# Steckkarte.net
KiCad netlist of a schematic drawn in EAGLE
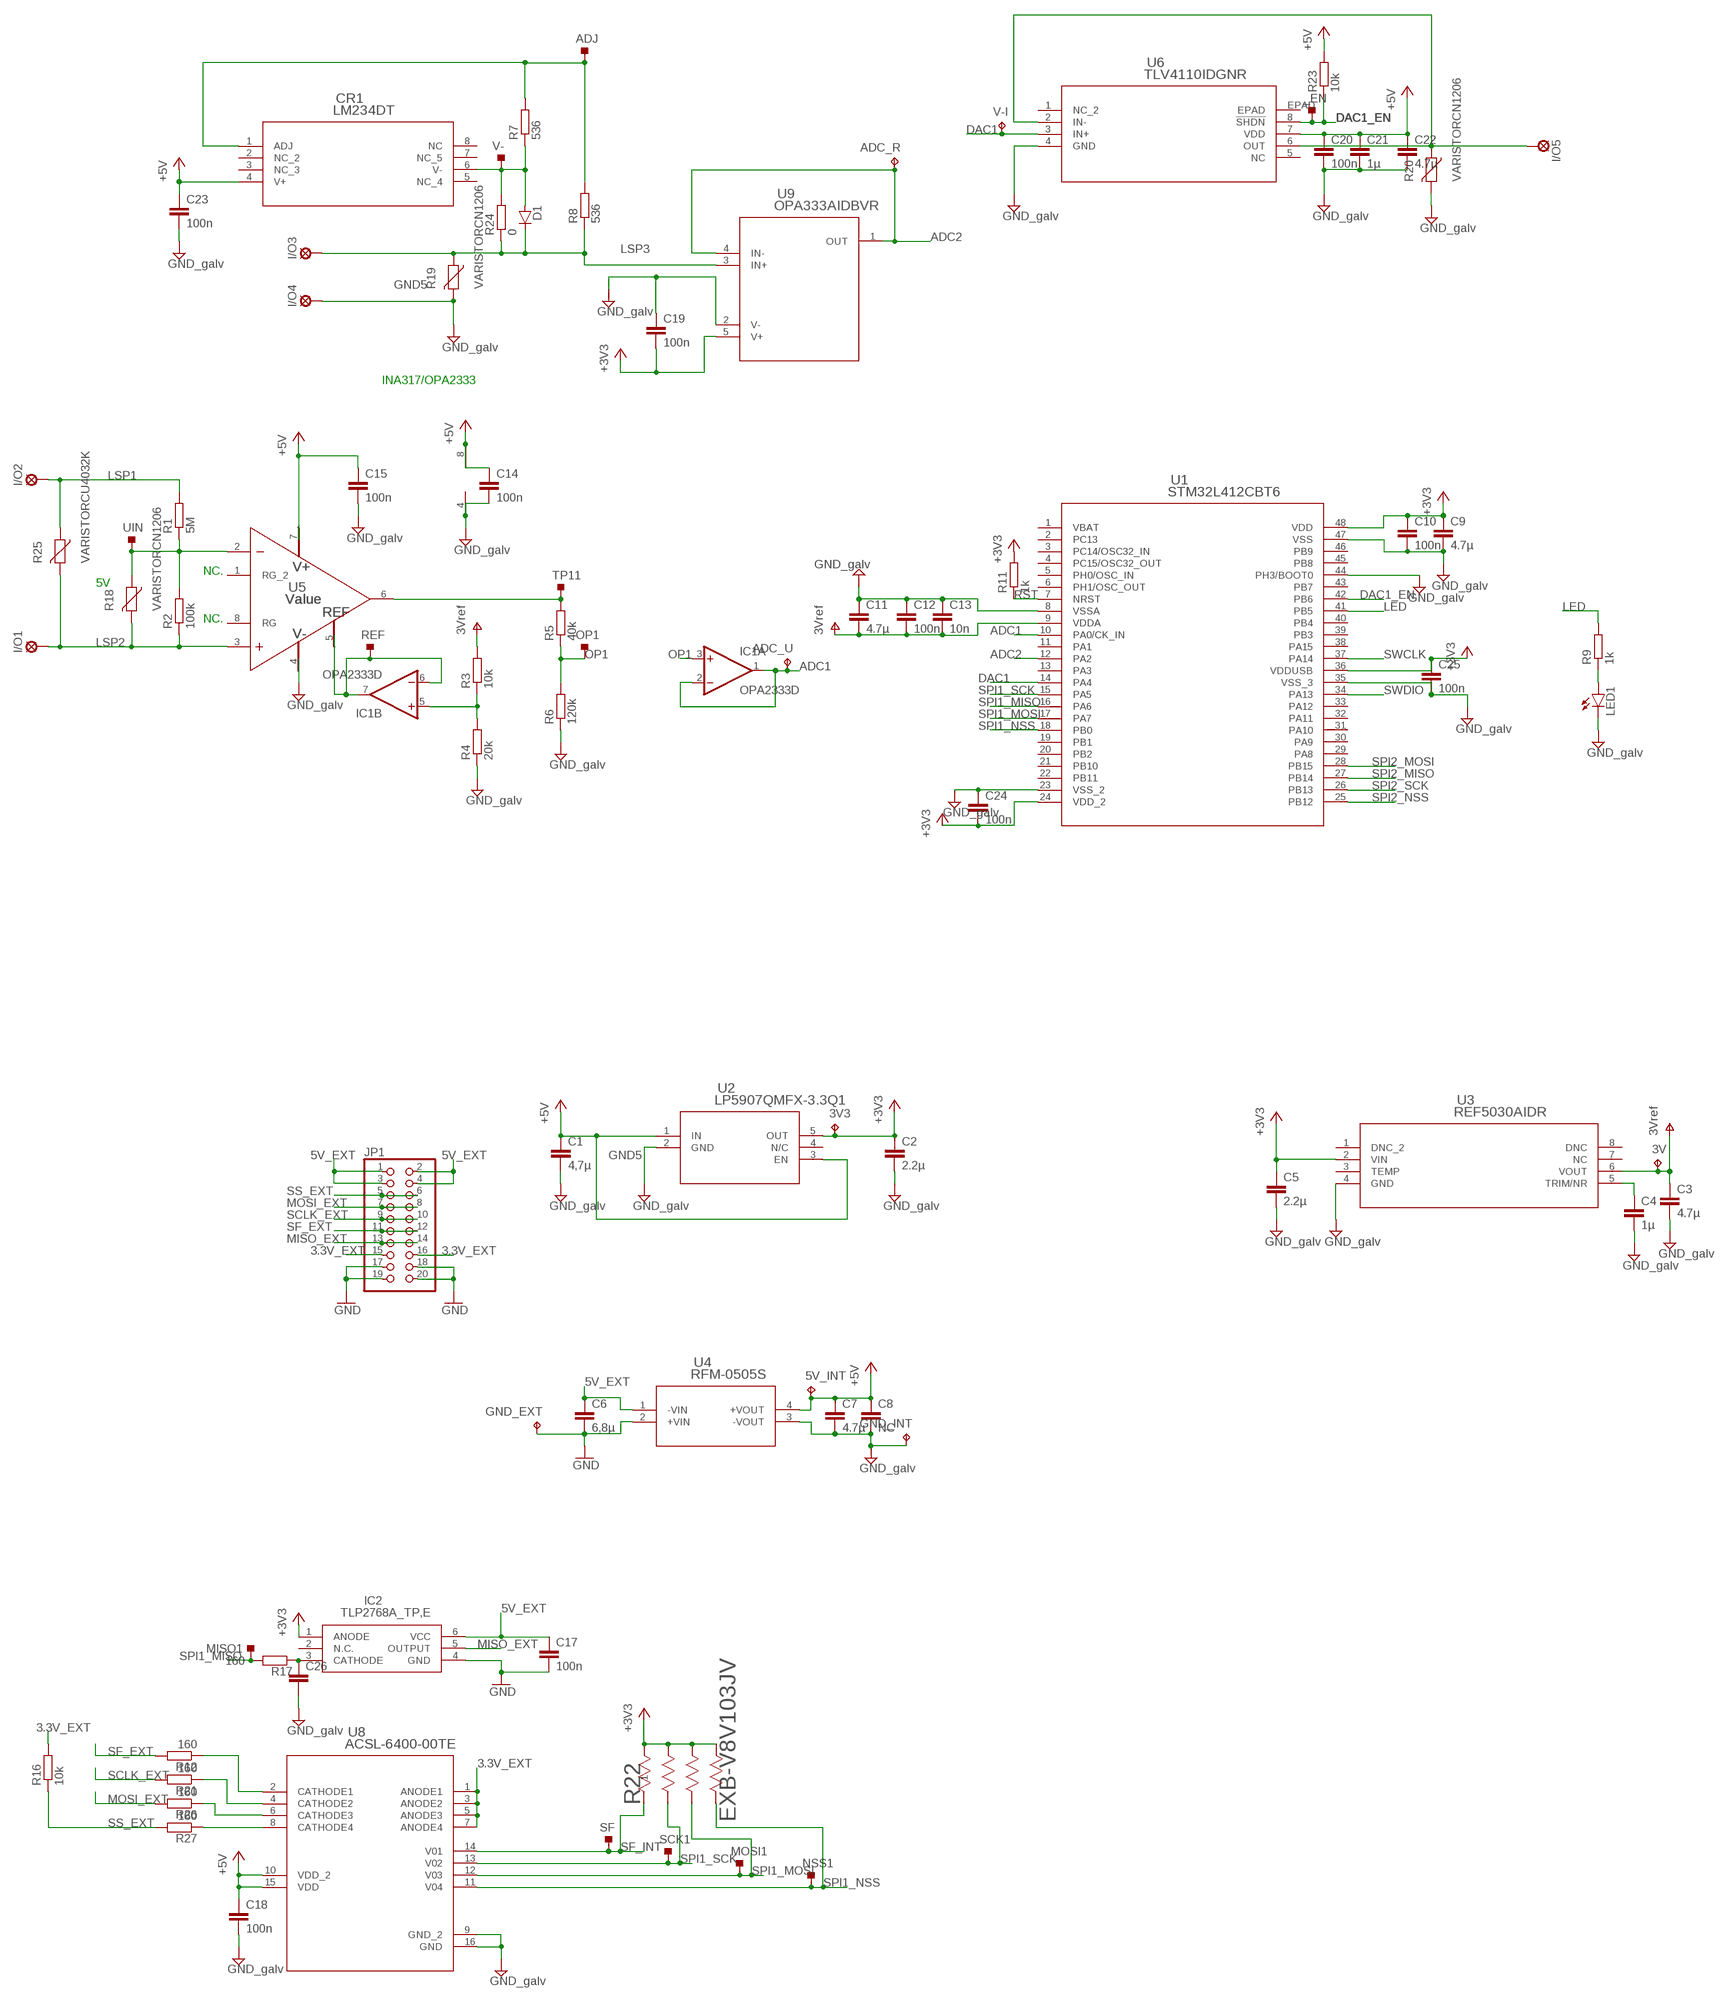
[diagram p0: schematic, sheet 1, part 1 of 2]
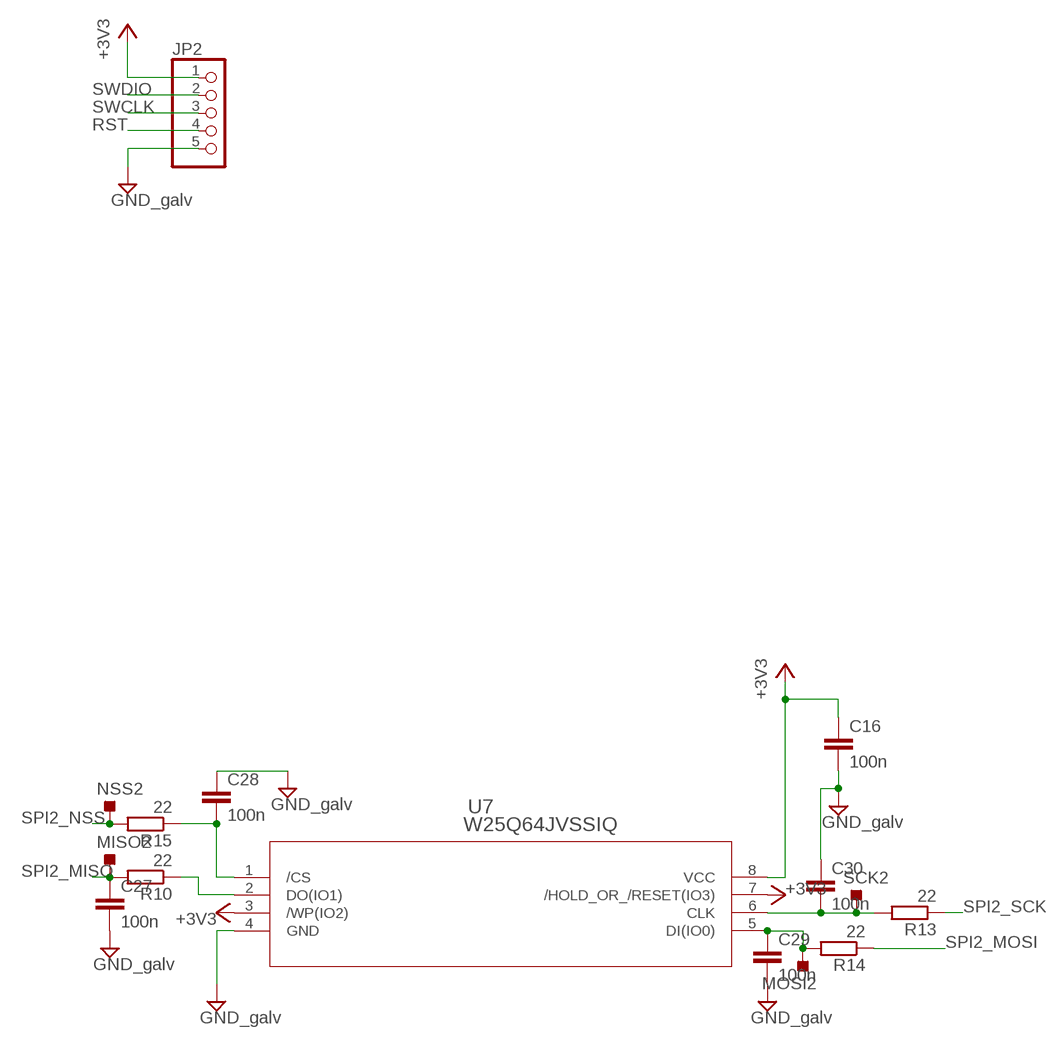
[diagram p1: schematic, sheet 1, part 2 of 2]

(export (version "E")
  (design (tool "Eeschema 10.0.6"))
  (components
    (comp (ref "3V")
      (value "TPPAD1-13")
      (footprint "eagle-import:P1-13")
      (libsource (lib "eagle-import") (part "TPPAD1-13"))
    )
    (comp (ref "3V3")
      (value "TPPAD1-13")
      (footprint "eagle-import:P1-13")
      (libsource (lib "eagle-import") (part "TPPAD1-13"))
    )
    (comp (ref "5V_INT")
      (value "TPPAD1-13")
      (footprint "eagle-import:P1-13")
      (libsource (lib "eagle-import") (part "TPPAD1-13"))
    )
    (comp (ref "ADC_R")
      (value "TPPAD1-13")
      (footprint "eagle-import:P1-13")
      (libsource (lib "eagle-import") (part "TPPAD1-13"))
    )
    (comp (ref "ADC_U")
      (value "TPPAD1-13")
      (footprint "eagle-import:P1-13")
      (libsource (lib "eagle-import") (part "TPPAD1-13"))
    )
    (comp (ref "ADJ")
      (value "TESTPOINT_TPS-SMD-10SN")
      (footprint "eagle-import:TESTPOINT_SMD-10SN")
      (libsource (lib "eagle-import") (part "TESTPOINT_TPS-SMD-10SN"))
    )
    (comp (ref "C1")
      (value "4,7µ")
      (footprint "eagle-import:C0603K")
      (libsource (lib "eagle-import") (part "C-EUC0603K"))
    )
    (comp (ref "C2")
      (value "2.2µ")
      (footprint "eagle-import:C0603K")
      (libsource (lib "eagle-import") (part "C-EUC0603K"))
    )
    (comp (ref "C3")
      (value "4.7µ")
      (footprint "eagle-import:C0603K")
      (libsource (lib "eagle-import") (part "C-EUC0603K"))
    )
    (comp (ref "C4")
      (value "1µ")
      (footprint "eagle-import:C0603K")
      (libsource (lib "eagle-import") (part "C-EUC0603K"))
    )
    (comp (ref "C5")
      (value "2.2µ")
      (footprint "eagle-import:C0603K")
      (libsource (lib "eagle-import") (part "C-EUC0603K"))
    )
    (comp (ref "C6")
      (value "6,8µ")
      (footprint "eagle-import:C0603K")
      (libsource (lib "eagle-import") (part "resistor_348_C-EUC0603K"))
    )
    (comp (ref "C7")
      (value "4.7µ")
      (footprint "eagle-import:C0603K")
      (libsource (lib "eagle-import") (part "resistor_348_C-EUC0603K"))
    )
    (comp (ref "C8")
      (value "NC")
      (footprint "eagle-import:C0603K")
      (libsource (lib "eagle-import") (part "resistor_348_C-EUC0603K"))
    )
    (comp (ref "C9")
      (value "4.7µ")
      (footprint "eagle-import:C0603K")
      (libsource (lib "eagle-import") (part "C-EUC0603K"))
    )
    (comp (ref "C10")
      (value "100n")
      (footprint "eagle-import:C0603K")
      (libsource (lib "eagle-import") (part "C-EUC0603K"))
    )
    (comp (ref "C11")
      (value "4.7µ")
      (footprint "eagle-import:C0603K")
      (libsource (lib "eagle-import") (part "C-EUC0603K"))
    )
    (comp (ref "C12")
      (value "100n")
      (footprint "eagle-import:C0603K")
      (libsource (lib "eagle-import") (part "C-EUC0603K"))
    )
    (comp (ref "C13")
      (value "10n")
      (footprint "eagle-import:C0603K")
      (libsource (lib "eagle-import") (part "C-EUC0603K"))
    )
    (comp (ref "C14")
      (value "100n")
      (footprint "eagle-import:C0603K")
      (libsource (lib "eagle-import") (part "C-EUC0603K"))
    )
    (comp (ref "C15")
      (value "100n")
      (footprint "eagle-import:C0603K")
      (libsource (lib "eagle-import") (part "C-EUC0603K"))
    )
    (comp (ref "C16")
      (value "100n")
      (footprint "eagle-import:C0603K")
      (libsource (lib "eagle-import") (part "C-EUC0603K"))
    )
    (comp (ref "C17")
      (value "100n")
      (footprint "eagle-import:C0603K")
      (libsource (lib "eagle-import") (part "C-EUC0603K"))
    )
    (comp (ref "C18")
      (value "100n")
      (footprint "eagle-import:C0603K")
      (libsource (lib "eagle-import") (part "C-EUC0603K"))
    )
    (comp (ref "C19")
      (value "100n")
      (footprint "eagle-import:C0603K")
      (libsource (lib "eagle-import") (part "C-EUC0603K"))
    )
    (comp (ref "C20")
      (value "100n")
      (footprint "eagle-import:C0603K")
      (libsource (lib "eagle-import") (part "C-EUC0603K"))
    )
    (comp (ref "C21")
      (value "1µ")
      (footprint "eagle-import:C0603K")
      (libsource (lib "eagle-import") (part "C-EUC0603K"))
    )
    (comp (ref "C22")
      (value "4.7µ")
      (footprint "eagle-import:C0603K")
      (libsource (lib "eagle-import") (part "C-EUC0603K"))
    )
    (comp (ref "C23")
      (value "100n")
      (footprint "eagle-import:C0603K")
      (libsource (lib "eagle-import") (part "C-EUC0603K"))
    )
    (comp (ref "C24")
      (value "100n")
      (footprint "eagle-import:C0603K")
      (libsource (lib "eagle-import") (part "C-EUC0603K"))
    )
    (comp (ref "C25")
      (value "100n")
      (footprint "eagle-import:C0603K")
      (libsource (lib "eagle-import") (part "C-EUC0603K"))
    )
    (comp (ref "C26")
      (value "C-EUC0603K")
      (footprint "eagle-import:C0603K")
      (libsource (lib "eagle-import") (part "C-EUC0603K"))
    )
    (comp (ref "C27")
      (value "100n")
      (footprint "eagle-import:C0603K")
      (libsource (lib "eagle-import") (part "C-EUC0603K"))
    )
    (comp (ref "C28")
      (value "100n")
      (footprint "eagle-import:C0603K")
      (libsource (lib "eagle-import") (part "C-EUC0603K"))
    )
    (comp (ref "C29")
      (value "100n")
      (footprint "eagle-import:C0603K")
      (libsource (lib "eagle-import") (part "C-EUC0603K"))
    )
    (comp (ref "C30")
      (value "100n")
      (footprint "eagle-import:C0603K")
      (libsource (lib "eagle-import") (part "C-EUC0603K"))
    )
    (comp (ref "CR1")
      (value "LM234DT")
      (footprint "eagle-import:SO-8")
      (libsource (lib "eagle-import") (part "LM234DT"))
    )
    (comp (ref "D1")
      (value "D-SOD123")
      (footprint "eagle-import:SOD123")
      (libsource (lib "eagle-import") (part "D-SOD123"))
    )
    (comp (ref "GND_EXT")
      (value "TPPAD1-13")
      (footprint "eagle-import:P1-13")
      (libsource (lib "eagle-import") (part "TPPAD1-13"))
    )
    (comp (ref "GND_INT")
      (value "TPPAD1-13")
      (footprint "eagle-import:P1-13")
      (libsource (lib "eagle-import") (part "TPPAD1-13"))
    )
    (comp (ref "I/O1")
      (value "SE14")
      (footprint "eagle-import:SE14")
      (libsource (lib "eagle-import") (part "SE14"))
    )
    (comp (ref "I/O2")
      (value "SE14")
      (footprint "eagle-import:SE14")
      (libsource (lib "eagle-import") (part "SE14"))
    )
    (comp (ref "I/O3")
      (value "SE14")
      (footprint "eagle-import:SE14")
      (libsource (lib "eagle-import") (part "SE14"))
    )
    (comp (ref "I/O4")
      (value "SE14")
      (footprint "eagle-import:SE14")
      (libsource (lib "eagle-import") (part "SE14"))
    )
    (comp (ref "I/O5")
      (value "SE14")
      (footprint "eagle-import:SE14")
      (libsource (lib "eagle-import") (part "SE14"))
    )
    (comp (ref "IC1")
      (value "OPA2333D")
      (footprint "eagle-import:SO08")
      (libsource (lib "eagle-import") (part "OPA2333D"))
    )
    (comp (ref "IC2")
      (value "TLP2768A_TP,E")
      (footprint "eagle-import:SOIC127P1000X220-6N")
      (fields
        (field (name "MANUFACTURER_PART_NUMBER") "TLP2768A(TP,E")
        (field (name "MOUSER_PART_NUMBER") "757-TLP2768ATPE")
      )
      (libsource (lib "eagle-import") (part "TLP2768A_TP,E"))
    )
    (comp (ref "JP1")
      (value "PINHD-2X10/90")
      (footprint "eagle-import:2X10_90")
      (libsource (lib "eagle-import") (part "PINHD-2X10/90"))
    )
    (comp (ref "JP2")
      (value "PINHD-1X5")
      (footprint "eagle-import:1X05")
      (libsource (lib "eagle-import") (part "PINHD-1X5"))
    )
    (comp (ref "LED1")
      (value "LED5MM")
      (footprint "eagle-import:LED5MM")
      (libsource (lib "eagle-import") (part "LED5MM"))
    )
    (comp (ref "MISO1")
      (value "TESTPOINT_TPS-SMD-10SN")
      (footprint "eagle-import:TESTPOINT_SMD-10SN")
      (libsource (lib "eagle-import") (part "TESTPOINT_TPS-SMD-10SN"))
    )
    (comp (ref "MISO2")
      (value "TESTPOINT_TPS-SMD-10SN")
      (footprint "eagle-import:TESTPOINT_SMD-10SN")
      (libsource (lib "eagle-import") (part "TESTPOINT_TPS-SMD-10SN"))
    )
    (comp (ref "MOSI1")
      (value "TESTPOINT_TPS-SMD-10SN")
      (footprint "eagle-import:TESTPOINT_SMD-10SN")
      (libsource (lib "eagle-import") (part "TESTPOINT_TPS-SMD-10SN"))
    )
    (comp (ref "MOSI2")
      (value "TESTPOINT_TPS-SMD-10SN")
      (footprint "eagle-import:TESTPOINT_SMD-10SN")
      (libsource (lib "eagle-import") (part "TESTPOINT_TPS-SMD-10SN"))
    )
    (comp (ref "NSS1")
      (value "TESTPOINT_TPS-SMD-10SN")
      (footprint "eagle-import:TESTPOINT_SMD-10SN")
      (libsource (lib "eagle-import") (part "TESTPOINT_TPS-SMD-10SN"))
    )
    (comp (ref "NSS2")
      (value "TESTPOINT_TPS-SMD-10SN")
      (footprint "eagle-import:TESTPOINT_SMD-10SN")
      (libsource (lib "eagle-import") (part "TESTPOINT_TPS-SMD-10SN"))
    )
    (comp (ref "OP1")
      (value "TESTPOINT_TPS-SMD-10SN")
      (footprint "eagle-import:TESTPOINT_SMD-10SN")
      (libsource (lib "eagle-import") (part "TESTPOINT_TPS-SMD-10SN"))
    )
    (comp (ref "R1")
      (value "5M")
      (footprint "eagle-import:R1206")
      (libsource (lib "eagle-import") (part "R-EU_R1206"))
    )
    (comp (ref "R2")
      (value "100k")
      (footprint "eagle-import:R1206")
      (libsource (lib "eagle-import") (part "R-EU_R1206"))
    )
    (comp (ref "R3")
      (value "10k")
      (footprint "eagle-import:R0603")
      (libsource (lib "eagle-import") (part "R-EU_R0603"))
    )
    (comp (ref "R4")
      (value "20k")
      (footprint "eagle-import:R0603")
      (libsource (lib "eagle-import") (part "R-EU_R0603"))
    )
    (comp (ref "R5")
      (value "40k")
      (footprint "eagle-import:R0603")
      (libsource (lib "eagle-import") (part "R-EU_R0603"))
    )
    (comp (ref "R6")
      (value "120k")
      (footprint "eagle-import:R0603")
      (libsource (lib "eagle-import") (part "R-EU_R0603"))
    )
    (comp (ref "R7")
      (value "536")
      (footprint "eagle-import:R0603")
      (libsource (lib "eagle-import") (part "R-EU_R0603"))
    )
    (comp (ref "R8")
      (value "536")
      (footprint "eagle-import:R0603")
      (libsource (lib "eagle-import") (part "R-EU_R0603"))
    )
    (comp (ref "R9")
      (value "1k")
      (footprint "eagle-import:R0603")
      (libsource (lib "eagle-import") (part "R-EU_R0603"))
    )
    (comp (ref "R10")
      (value "22")
      (footprint "eagle-import:R0603")
      (libsource (lib "eagle-import") (part "R-EU_R0603"))
    )
    (comp (ref "R11")
      (value "1k")
      (footprint "eagle-import:R0603")
      (libsource (lib "eagle-import") (part "R-EU_R0603"))
    )
    (comp (ref "R12")
      (value "160")
      (footprint "eagle-import:R0603")
      (libsource (lib "eagle-import") (part "R-EU_R0603"))
    )
    (comp (ref "R13")
      (value "22")
      (footprint "eagle-import:R0603")
      (libsource (lib "eagle-import") (part "R-EU_R0603"))
    )
    (comp (ref "R14")
      (value "22")
      (footprint "eagle-import:R0603")
      (libsource (lib "eagle-import") (part "R-EU_R0603"))
    )
    (comp (ref "R15")
      (value "22")
      (footprint "eagle-import:R0603")
      (libsource (lib "eagle-import") (part "R-EU_R0603"))
    )
    (comp (ref "R16")
      (value "10k")
      (footprint "eagle-import:R0603")
      (libsource (lib "eagle-import") (part "R-EU_R0603"))
    )
    (comp (ref "R17")
      (value "160")
      (footprint "eagle-import:R0603")
      (libsource (lib "eagle-import") (part "R-EU_R0603"))
    )
    (comp (ref "R18")
      (value "VARISTORCN1206")
      (footprint "eagle-import:CT_CN1206")
      (libsource (lib "eagle-import") (part "VARISTORCN1206"))
    )
    (comp (ref "R19")
      (value "VARISTORCN1206")
      (footprint "eagle-import:CT_CN1206")
      (libsource (lib "eagle-import") (part "VARISTORCN1206"))
    )
    (comp (ref "R20")
      (value "VARISTORCN1206")
      (footprint "eagle-import:CT_CN1206")
      (libsource (lib "eagle-import") (part "VARISTORCN1206"))
    )
    (comp (ref "R21")
      (value "160")
      (footprint "eagle-import:R0603")
      (libsource (lib "eagle-import") (part "R-EU_R0603"))
    )
    (comp (ref "R22")
      (value "EXB-V8V103JV")
      (footprint "eagle-import:EXBV8V")
      (libsource (lib "eagle-import") (part "EXB-V8V103JV"))
    )
    (comp (ref "R23")
      (value "10k")
      (footprint "eagle-import:R0603")
      (libsource (lib "eagle-import") (part "R-EU_R0603"))
    )
    (comp (ref "R24")
      (value "0")
      (footprint "eagle-import:R0603")
      (libsource (lib "eagle-import") (part "R-EU_R0603"))
    )
    (comp (ref "R25")
      (value "VARISTORCU4032K")
      (footprint "eagle-import:CU4032K")
      (libsource (lib "eagle-import") (part "VARISTORCU4032K"))
    )
    (comp (ref "R26")
      (value "160")
      (footprint "eagle-import:R0603")
      (libsource (lib "eagle-import") (part "R-EU_R0603"))
    )
    (comp (ref "R27")
      (value "160")
      (footprint "eagle-import:R0603")
      (libsource (lib "eagle-import") (part "R-EU_R0603"))
    )
    (comp (ref "REF")
      (value "TESTPOINT_TPS-SMD-10SN")
      (footprint "eagle-import:TESTPOINT_SMD-10SN")
      (libsource (lib "eagle-import") (part "TESTPOINT_TPS-SMD-10SN"))
    )
    (comp (ref "SCK1")
      (value "TESTPOINT_TPS-SMD-10SN")
      (footprint "eagle-import:TESTPOINT_SMD-10SN")
      (libsource (lib "eagle-import") (part "TESTPOINT_TPS-SMD-10SN"))
    )
    (comp (ref "SCK2")
      (value "TESTPOINT_TPS-SMD-10SN")
      (footprint "eagle-import:TESTPOINT_SMD-10SN")
      (libsource (lib "eagle-import") (part "TESTPOINT_TPS-SMD-10SN"))
    )
    (comp (ref "SF")
      (value "TESTPOINT_TPS-SMD-10SN")
      (footprint "eagle-import:TESTPOINT_SMD-10SN")
      (libsource (lib "eagle-import") (part "TESTPOINT_TPS-SMD-10SN"))
    )
    (comp (ref "TP11")
      (value "TESTPOINT_TPS-SMD-10SN")
      (footprint "eagle-import:TESTPOINT_SMD-10SN")
      (libsource (lib "eagle-import") (part "TESTPOINT_TPS-SMD-10SN"))
    )
    (comp (ref "U1")
      (value "STM32L412CBT6")
      (footprint "eagle-import:LQFP-48")
      (fields (field (name "COPYRIGHT") "Copyright (C) 2018 Accelerated Designs. All rights reserved"))
      (libsource (lib "eagle-import") (part "STM32L412CBT6"))
    )
    (comp (ref "U2")
      (value "LP5907QMFX-3.3Q1")
      (footprint "eagle-import:DBV5")
      (libsource (lib "eagle-import") (part "LP5907QMFX-3.3Q1"))
    )
    (comp (ref "U3")
      (value "REF5030AIDR")
      (footprint "eagle-import:D8")
      (libsource (lib "eagle-import") (part "REF5030AIDR"))
    )
    (comp (ref "U4")
      (value "RFM-0505S")
      (footprint "eagle-import:RFM-0505S")
      (fields (field (name "COPYRIGHT") "Copyright (C) 2018 Accelerated Designs. All rights reserved"))
      (libsource (lib "eagle-import") (part "RFM-0505S"))
    )
    (comp (ref "U5")
      (value "Value")
      (footprint "eagle-import:DGK0008A_N")
      (fields (field (name "MANUFACTURER") "Texas Instruments") (field (name "PARTNUMBER") "INA317IDGKR"))
      (libsource (lib "eagle-import") (part "INA317IDGKR"))
    )
    (comp (ref "U6")
      (value "TLV4110IDGNR")
      (footprint "eagle-import:DGN8_1P89X1P57")
      (fields
        (field (name "GENERIC_PART_NUMBER") "TLV4110")
        (field (name "MANUFACTURER") "Texas Instruments")
      )
      (libsource (lib "eagle-import") (part "TLV4110IDGNR"))
    )
    (comp (ref "U7")
      (value "W25Q64JVSSIQ")
      (footprint "eagle-import:SOIC-8_5P28X5P28")
      (fields (field (name "COPYRIGHT") "Copyright (C) 2018 Accelerated Designs. All rights reserved"))
      (libsource (lib "eagle-import") (part "W25Q64JVSSIQ"))
    )
    (comp (ref "U8")
      (value "ACSL-6400-00TE")
      (footprint "eagle-import:SOIC_6400-00TE")
      (fields (field (name "COPYRIGHT") "Copyright (C) 2018 Accelerated Designs. All rights reserved"))
      (libsource (lib "eagle-import") (part "ACSL-6400-00TE"))
    )
    (comp (ref "U9")
      (value "OPA333AIDBVR")
      (footprint "eagle-import:DBV5")
      (fields (field (name "GENERIC_PART_NUMBER") "OPA333") (field (name "MANUFACTURER") "Texas Instruments"))
      (libsource (lib "eagle-import") (part "OPA333AIDBVR"))
    )
    (comp (ref "UIN")
      (value "TESTPOINT_TPS-SMD-10SN")
      (footprint "eagle-import:TESTPOINT_SMD-10SN")
      (libsource (lib "eagle-import") (part "TESTPOINT_TPS-SMD-10SN"))
    )
    (comp (ref "V-")
      (value "TESTPOINT_TPS-SMD-10SN")
      (footprint "eagle-import:TESTPOINT_SMD-10SN")
      (libsource (lib "eagle-import") (part "TESTPOINT_TPS-SMD-10SN"))
    )
    (comp (ref "V-I")
      (value "TPPAD1-13")
      (footprint "eagle-import:P1-13")
      (libsource (lib "eagle-import") (part "TPPAD1-13"))
    )
    (comp (ref "_EN")
      (value "TESTPOINT_TPS-SMD-10SN")
      (footprint "eagle-import:TESTPOINT_SMD-10SN")
      (libsource (lib "eagle-import") (part "TESTPOINT_TPS-SMD-10SN"))
    )
  )
  (nets
    (net (code "1") (name "+3V3") (class "Default")
      (node (ref "3V3") (pin "TP") (pinfunction "TP_TP") (pintype "input"))
      (node (ref "C10") (pin "1") (pinfunction "1_1") (pintype "passive"))
      (node (ref "C16") (pin "1") (pinfunction "1_1") (pintype "passive"))
      (node (ref "C19") (pin "2") (pinfunction "2_2") (pintype "passive"))
      (node (ref "C2") (pin "1") (pinfunction "1_1") (pintype "passive"))
      (node (ref "C24") (pin "2") (pinfunction "2_2") (pintype "passive"))
      (node (ref "C25") (pin "1") (pinfunction "1_1") (pintype "passive"))
      (node (ref "C5") (pin "1") (pinfunction "1_1") (pintype "passive"))
      (node (ref "C9") (pin "1") (pinfunction "1_1") (pintype "passive"))
      (node (ref "IC2") (pin "1") (pinfunction "ANODE_1") (pintype "bidirectional"))
      (node (ref "JP2") (pin "1") (pinfunction "1_1") (pintype "passive"))
      (node (ref "R11") (pin "2") (pinfunction "2_2") (pintype "passive"))
      (node (ref "R22") (pin "5") (pinfunction "5_5") (pintype "passive"))
      (node (ref "R22") (pin "6") (pinfunction "6_6") (pintype "passive"))
      (node (ref "R22") (pin "7") (pinfunction "7_7") (pintype "passive"))
      (node (ref "R22") (pin "8") (pinfunction "8_8") (pintype "passive"))
      (node (ref "U1") (pin "24") (pinfunction "VDD_2_24") (pintype "power_in"))
      (node (ref "U1") (pin "36") (pinfunction "VDDUSB_36") (pintype "power_in"))
      (node (ref "U1") (pin "48") (pinfunction "VDD_48") (pintype "power_in"))
      (node (ref "U2") (pin "5") (pinfunction "OUT_5") (pintype "output"))
      (node (ref "U3") (pin "2") (pinfunction "VIN_2") (pintype "input"))
      (node (ref "U7") (pin "3") (pinfunction "/WP(IO2)_3") (pintype "passive"))
      (node (ref "U7") (pin "7") (pinfunction "/HOLD_OR_/RESET(IO3)_7") (pintype "passive"))
      (node (ref "U7") (pin "8") (pinfunction "VCC_8") (pintype "power_in"))
      (node (ref "U9") (pin "5") (pinfunction "V+_5") (pintype "power_in"))
    )
    (net (code "2") (name "+5V") (class "Default")
      (node (ref "5V_INT") (pin "TP") (pinfunction "TP_TP") (pintype "input"))
      (node (ref "C1") (pin "1") (pinfunction "1_1") (pintype "passive"))
      (node (ref "C14") (pin "1") (pinfunction "1_1") (pintype "passive"))
      (node (ref "C15") (pin "1") (pinfunction "1_1") (pintype "passive"))
      (node (ref "C18") (pin "1") (pinfunction "1_1") (pintype "passive"))
      (node (ref "C20") (pin "1") (pinfunction "1_1") (pintype "passive"))
      (node (ref "C21") (pin "1") (pinfunction "1_1") (pintype "passive"))
      (node (ref "C22") (pin "1") (pinfunction "1_1") (pintype "passive"))
      (node (ref "C23") (pin "1") (pinfunction "1_1") (pintype "passive"))
      (node (ref "C7") (pin "1") (pinfunction "1_1") (pintype "passive"))
      (node (ref "C8") (pin "1") (pinfunction "1_1") (pintype "passive"))
      (node (ref "CR1") (pin "4") (pinfunction "V+_4") (pintype "power_in"))
      (node (ref "IC1") (pin "8") (pinfunction "V+_8") (pintype "power_in"))
      (node (ref "R23") (pin "2") (pinfunction "2_2") (pintype "passive"))
      (node (ref "U2") (pin "1") (pinfunction "IN_1") (pintype "input"))
      (node (ref "U2") (pin "3") (pinfunction "EN_3") (pintype "input"))
      (node (ref "U4") (pin "4") (pinfunction "+VOUT_4") (pintype "output"))
      (node (ref "U5") (pin "7") (pinfunction "V+_7") (pintype "power_in"))
      (node (ref "U6") (pin "7") (pinfunction "VDD_7") (pintype "power_in"))
      (node (ref "U8") (pin "10") (pinfunction "VDD_2_10") (pintype "power_in"))
      (node (ref "U8") (pin "15") (pinfunction "VDD_15") (pintype "power_in"))
    )
    (net (code "3") (name "/3.3V_EXT") (class "Default")
      (node (ref "JP1") (pin "15") (pinfunction "15_15") (pintype "passive"))
      (node (ref "JP1") (pin "16") (pinfunction "16_16") (pintype "passive"))
      (node (ref "R16") (pin "2") (pinfunction "2_2") (pintype "passive"))
      (node (ref "U8") (pin "1") (pinfunction "ANODE1_1") (pintype "bidirectional"))
      (node (ref "U8") (pin "3") (pinfunction "ANODE2_3") (pintype "bidirectional"))
      (node (ref "U8") (pin "5") (pinfunction "ANODE3_5") (pintype "bidirectional"))
      (node (ref "U8") (pin "7") (pinfunction "ANODE4_7") (pintype "bidirectional"))
    )
    (net (code "4") (name "/5V_EXT") (class "Default")
      (node (ref "C17") (pin "1") (pinfunction "1_1") (pintype "passive"))
      (node (ref "C6") (pin "1") (pinfunction "1_1") (pintype "passive"))
      (node (ref "IC2") (pin "6") (pinfunction "VCC_6") (pintype "bidirectional"))
      (node (ref "JP1") (pin "1") (pinfunction "1_1") (pintype "passive"))
      (node (ref "JP1") (pin "2") (pinfunction "2_2") (pintype "passive"))
      (node (ref "JP1") (pin "3") (pinfunction "3_3") (pintype "passive"))
      (node (ref "JP1") (pin "4") (pinfunction "4_4") (pintype "passive"))
      (node (ref "U4") (pin "1") (pinfunction "-VIN_1") (pintype "input"))
    )
    (net (code "5") (name "/ADC1") (class "Default")
      (node (ref "ADC_U") (pin "TP") (pinfunction "TP_TP") (pintype "input"))
      (node (ref "IC1") (pin "1") (pinfunction "OUT_1") (pintype "output"))
      (node (ref "IC1") (pin "2") (pinfunction "-IN_2") (pintype "input"))
      (node (ref "U1") (pin "10") (pinfunction "PA0/CK_IN_10") (pintype "bidirectional"))
    )
    (net (code "6") (name "/ADC2") (class "Default")
      (node (ref "ADC_R") (pin "TP") (pinfunction "TP_TP") (pintype "input"))
      (node (ref "U1") (pin "12") (pinfunction "PA2_12") (pintype "bidirectional"))
      (node (ref "U9") (pin "1") (pinfunction "OUT_1") (pintype "output"))
      (node (ref "U9") (pin "4") (pinfunction "IN-_4") (pintype "input"))
    )
    (net (code "7") (name "/DAC1") (class "Default")
      (node (ref "U1") (pin "14") (pinfunction "PA4_14") (pintype "bidirectional"))
      (node (ref "U6") (pin "3") (pinfunction "IN+_3") (pintype "input"))
      (node (ref "V-I") (pin "TP") (pinfunction "TP_TP") (pintype "input"))
    )
    (net (code "8") (name "/DAC1_EN") (class "Default")
      (node (ref "R23") (pin "1") (pinfunction "1_1") (pintype "passive"))
      (node (ref "U1") (pin "42") (pinfunction "PB6_42") (pintype "bidirectional"))
      (node (ref "U6") (pin "8") (pinfunction "~{SHDN}_8") (pintype "passive"))
      (node (ref "_EN") (pin "TP") (pinfunction "TP_TP") (pintype "passive"))
    )
    (net (code "9") (name "/LED") (class "Default")
      (node (ref "R9") (pin "2") (pinfunction "2_2") (pintype "passive"))
      (node (ref "U1") (pin "41") (pinfunction "PB5_41") (pintype "bidirectional"))
    )
    (net (code "10") (name "/LSP1") (class "Default")
      (node (ref "I/O2") (pin "MP") (pinfunction "MP_MP") (pintype "passive"))
      (node (ref "R1") (pin "2") (pinfunction "2_2") (pintype "passive"))
      (node (ref "R25") (pin "1") (pinfunction "1_1") (pintype "passive"))
    )
    (net (code "11") (name "/LSP2") (class "Default")
      (node (ref "I/O1") (pin "MP") (pinfunction "MP_MP") (pintype "passive"))
      (node (ref "R18") (pin "2") (pinfunction "2_2") (pintype "passive"))
      (node (ref "R2") (pin "1") (pinfunction "1_1") (pintype "passive"))
      (node (ref "R25") (pin "2") (pinfunction "2_2") (pintype "passive"))
      (node (ref "U5") (pin "3") (pinfunction "IN+_3") (pintype "input"))
    )
    (net (code "12") (name "/LSP3") (class "Default")
      (node (ref "D1") (pin "1") (pinfunction "C_1") (pintype "passive"))
      (node (ref "I/O3") (pin "MP") (pinfunction "MP_MP") (pintype "passive"))
      (node (ref "R19") (pin "1") (pinfunction "1_1") (pintype "passive"))
      (node (ref "R24") (pin "1") (pinfunction "1_1") (pintype "passive"))
      (node (ref "R8") (pin "1") (pinfunction "1_1") (pintype "passive"))
      (node (ref "U9") (pin "3") (pinfunction "IN+_3") (pintype "input"))
    )
    (net (code "13") (name "/MISO_EXT") (class "Default")
      (node (ref "IC2") (pin "5") (pinfunction "OUTPUT_5") (pintype "bidirectional"))
      (node (ref "JP1") (pin "13") (pinfunction "13_13") (pintype "passive"))
      (node (ref "JP1") (pin "14") (pinfunction "14_14") (pintype "passive"))
    )
    (net (code "14") (name "/MOSI_EXT") (class "Default")
      (node (ref "JP1") (pin "7") (pinfunction "7_7") (pintype "passive"))
      (node (ref "JP1") (pin "8") (pinfunction "8_8") (pintype "passive"))
      (node (ref "R26") (pin "2") (pinfunction "2_2") (pintype "passive"))
    )
    (net (code "15") (name "/OP1") (class "Default")
      (node (ref "IC1") (pin "3") (pinfunction "+IN_3") (pintype "input"))
      (node (ref "OP1") (pin "TP") (pinfunction "TP_TP") (pintype "passive"))
      (node (ref "R5") (pin "1") (pinfunction "1_1") (pintype "passive"))
      (node (ref "R6") (pin "2") (pinfunction "2_2") (pintype "passive"))
    )
    (net (code "16") (name "/RST") (class "Default")
      (node (ref "JP2") (pin "4") (pinfunction "4_4") (pintype "passive"))
      (node (ref "R11") (pin "1") (pinfunction "1_1") (pintype "passive"))
      (node (ref "U1") (pin "7") (pinfunction "NRST_7") (pintype "bidirectional"))
    )
    (net (code "17") (name "/SCLK_EXT") (class "Default")
      (node (ref "JP1") (pin "10") (pinfunction "10_10") (pintype "passive"))
      (node (ref "JP1") (pin "9") (pinfunction "9_9") (pintype "passive"))
      (node (ref "R21") (pin "2") (pinfunction "2_2") (pintype "passive"))
    )
    (net (code "18") (name "/SF_EXT") (class "Default")
      (node (ref "JP1") (pin "11") (pinfunction "11_11") (pintype "passive"))
      (node (ref "JP1") (pin "12") (pinfunction "12_12") (pintype "passive"))
      (node (ref "R12") (pin "2") (pinfunction "2_2") (pintype "passive"))
    )
    (net (code "19") (name "/SF_INT") (class "Default")
      (node (ref "R22") (pin "1") (pinfunction "1_1") (pintype "passive"))
      (node (ref "SF") (pin "TP") (pinfunction "TP_TP") (pintype "passive"))
      (node (ref "U8") (pin "14") (pinfunction "V01_14") (pintype "bidirectional"))
    )
    (net (code "20") (name "/SPI1_MISO") (class "Default")
      (node (ref "MISO1") (pin "TP") (pinfunction "TP_TP") (pintype "passive"))
      (node (ref "R17") (pin "2") (pinfunction "2_2") (pintype "passive"))
      (node (ref "U1") (pin "16") (pinfunction "PA6_16") (pintype "bidirectional"))
    )
    (net (code "21") (name "/SPI1_MOSI") (class "Default")
      (node (ref "MOSI1") (pin "TP") (pinfunction "TP_TP") (pintype "passive"))
      (node (ref "R22") (pin "3") (pinfunction "3_3") (pintype "passive"))
      (node (ref "U1") (pin "17") (pinfunction "PA7_17") (pintype "bidirectional"))
      (node (ref "U8") (pin "12") (pinfunction "V03_12") (pintype "bidirectional"))
    )
    (net (code "22") (name "/SPI1_NSS") (class "Default")
      (node (ref "NSS1") (pin "TP") (pinfunction "TP_TP") (pintype "passive"))
      (node (ref "R22") (pin "4") (pinfunction "4_4") (pintype "passive"))
      (node (ref "U1") (pin "18") (pinfunction "PB0_18") (pintype "bidirectional"))
      (node (ref "U8") (pin "11") (pinfunction "V04_11") (pintype "bidirectional"))
    )
    (net (code "23") (name "/SPI1_SCK") (class "Default")
      (node (ref "R22") (pin "2") (pinfunction "2_2") (pintype "passive"))
      (node (ref "SCK1") (pin "TP") (pinfunction "TP_TP") (pintype "passive"))
      (node (ref "U1") (pin "15") (pinfunction "PA5_15") (pintype "bidirectional"))
      (node (ref "U8") (pin "13") (pinfunction "V02_13") (pintype "bidirectional"))
    )
    (net (code "24") (name "/SPI2_MISO") (class "Default")
      (node (ref "C27") (pin "1") (pinfunction "1_1") (pintype "passive"))
      (node (ref "MISO2") (pin "TP") (pinfunction "TP_TP") (pintype "passive"))
      (node (ref "R10") (pin "2") (pinfunction "2_2") (pintype "passive"))
      (node (ref "U1") (pin "27") (pinfunction "PB14_27") (pintype "bidirectional"))
    )
    (net (code "25") (name "/SPI2_MOSI") (class "Default")
      (node (ref "R14") (pin "1") (pinfunction "1_1") (pintype "passive"))
      (node (ref "U1") (pin "28") (pinfunction "PB15_28") (pintype "bidirectional"))
    )
    (net (code "26") (name "/SPI2_NSS") (class "Default")
      (node (ref "NSS2") (pin "TP") (pinfunction "TP_TP") (pintype "passive"))
      (node (ref "R15") (pin "2") (pinfunction "2_2") (pintype "passive"))
      (node (ref "U1") (pin "25") (pinfunction "PB12_25") (pintype "bidirectional"))
    )
    (net (code "27") (name "/SPI2_SCK") (class "Default")
      (node (ref "R13") (pin "1") (pinfunction "1_1") (pintype "passive"))
      (node (ref "U1") (pin "26") (pinfunction "PB13_26") (pintype "bidirectional"))
    )
    (net (code "28") (name "/SS_EXT") (class "Default")
      (node (ref "JP1") (pin "5") (pinfunction "5_5") (pintype "passive"))
      (node (ref "JP1") (pin "6") (pinfunction "6_6") (pintype "passive"))
      (node (ref "R16") (pin "1") (pinfunction "1_1") (pintype "passive"))
      (node (ref "R27") (pin "2") (pinfunction "2_2") (pintype "passive"))
    )
    (net (code "29") (name "/SWCLK") (class "Default")
      (node (ref "JP2") (pin "3") (pinfunction "3_3") (pintype "passive"))
      (node (ref "U1") (pin "37") (pinfunction "PA14_37") (pintype "bidirectional"))
    )
    (net (code "30") (name "/SWDIO") (class "Default")
      (node (ref "JP2") (pin "2") (pinfunction "2_2") (pintype "passive"))
      (node (ref "U1") (pin "34") (pinfunction "PA13_34") (pintype "bidirectional"))
    )
    (net (code "31") (name "/VBAT") (class "Default")
      (node (ref "U1") (pin "1") (pinfunction "VBAT_1") (pintype "power_in"))
    )
    (net (code "32") (name "3Vref") (class "Default")
      (node (ref "3V") (pin "TP") (pinfunction "TP_TP") (pintype "input"))
      (node (ref "C11") (pin "2") (pinfunction "2_2") (pintype "passive"))
      (node (ref "C12") (pin "2") (pinfunction "2_2") (pintype "passive"))
      (node (ref "C13") (pin "2") (pinfunction "2_2") (pintype "passive"))
      (node (ref "C3") (pin "1") (pinfunction "1_1") (pintype "passive"))
      (node (ref "R3") (pin "2") (pinfunction "2_2") (pintype "passive"))
      (node (ref "U1") (pin "9") (pinfunction "VDDA_9") (pintype "power_in"))
      (node (ref "U3") (pin "6") (pinfunction "VOUT_6") (pintype "output"))
    )
    (net (code "33") (name "GND") (class "Default")
      (node (ref "C17") (pin "2") (pinfunction "2_2") (pintype "passive"))
      (node (ref "C6") (pin "2") (pinfunction "2_2") (pintype "passive"))
      (node (ref "GND_EXT") (pin "TP") (pinfunction "TP_TP") (pintype "input"))
      (node (ref "IC2") (pin "4") (pinfunction "GND_4") (pintype "bidirectional"))
      (node (ref "JP1") (pin "17") (pinfunction "17_17") (pintype "passive"))
      (node (ref "JP1") (pin "18") (pinfunction "18_18") (pintype "passive"))
      (node (ref "JP1") (pin "19") (pinfunction "19_19") (pintype "passive"))
      (node (ref "JP1") (pin "20") (pinfunction "20_20") (pintype "passive"))
      (node (ref "U4") (pin "2") (pinfunction "+VIN_2") (pintype "input"))
    )
    (net (code "34") (name "GND_galv") (class "Default")
      (node (ref "C1") (pin "2") (pinfunction "2_2") (pintype "passive"))
      (node (ref "C10") (pin "2") (pinfunction "2_2") (pintype "passive"))
      (node (ref "C11") (pin "1") (pinfunction "1_1") (pintype "passive"))
      (node (ref "C12") (pin "1") (pinfunction "1_1") (pintype "passive"))
      (node (ref "C13") (pin "1") (pinfunction "1_1") (pintype "passive"))
      (node (ref "C14") (pin "2") (pinfunction "2_2") (pintype "passive"))
      (node (ref "C15") (pin "2") (pinfunction "2_2") (pintype "passive"))
      (node (ref "C16") (pin "2") (pinfunction "2_2") (pintype "passive"))
      (node (ref "C18") (pin "2") (pinfunction "2_2") (pintype "passive"))
      (node (ref "C19") (pin "1") (pinfunction "1_1") (pintype "passive"))
      (node (ref "C2") (pin "2") (pinfunction "2_2") (pintype "passive"))
      (node (ref "C20") (pin "2") (pinfunction "2_2") (pintype "passive"))
      (node (ref "C21") (pin "2") (pinfunction "2_2") (pintype "passive"))
      (node (ref "C22") (pin "2") (pinfunction "2_2") (pintype "passive"))
      (node (ref "C23") (pin "2") (pinfunction "2_2") (pintype "passive"))
      (node (ref "C24") (pin "1") (pinfunction "1_1") (pintype "passive"))
      (node (ref "C25") (pin "2") (pinfunction "2_2") (pintype "passive"))
      (node (ref "C26") (pin "2") (pinfunction "2_2") (pintype "passive"))
      (node (ref "C27") (pin "2") (pinfunction "2_2") (pintype "passive"))
      (node (ref "C28") (pin "1") (pinfunction "1_1") (pintype "passive"))
      (node (ref "C29") (pin "2") (pinfunction "2_2") (pintype "passive"))
      (node (ref "C3") (pin "2") (pinfunction "2_2") (pintype "passive"))
      (node (ref "C30") (pin "1") (pinfunction "1_1") (pintype "passive"))
      (node (ref "C4") (pin "2") (pinfunction "2_2") (pintype "passive"))
      (node (ref "C5") (pin "2") (pinfunction "2_2") (pintype "passive"))
      (node (ref "C7") (pin "2") (pinfunction "2_2") (pintype "passive"))
      (node (ref "C8") (pin "2") (pinfunction "2_2") (pintype "passive"))
      (node (ref "C9") (pin "2") (pinfunction "2_2") (pintype "passive"))
      (node (ref "GND_INT") (pin "TP") (pinfunction "TP_TP") (pintype "input"))
      (node (ref "I/O4") (pin "MP") (pinfunction "MP_MP") (pintype "passive"))
      (node (ref "IC1") (pin "4") (pinfunction "V-_4") (pintype "power_in"))
      (node (ref "JP2") (pin "5") (pinfunction "5_5") (pintype "passive"))
      (node (ref "LED1") (pin "K") (pinfunction "C_K") (pintype "passive"))
      (node (ref "R19") (pin "2") (pinfunction "2_2") (pintype "passive"))
      (node (ref "R20") (pin "2") (pinfunction "2_2") (pintype "passive"))
      (node (ref "R4") (pin "1") (pinfunction "1_1") (pintype "passive"))
      (node (ref "R6") (pin "1") (pinfunction "1_1") (pintype "passive"))
      (node (ref "U1") (pin "23") (pinfunction "VSS_2_23") (pintype "power_in"))
      (node (ref "U1") (pin "35") (pinfunction "VSS_3_35") (pintype "power_in"))
      (node (ref "U1") (pin "44") (pinfunction "PH3/BOOT0_44") (pintype "bidirectional"))
      (node (ref "U1") (pin "47") (pinfunction "VSS_47") (pintype "power_in"))
      (node (ref "U1") (pin "8") (pinfunction "VSSA_8") (pintype "power_in"))
      (node (ref "U2") (pin "2") (pinfunction "GND_2") (pintype "power_in"))
      (node (ref "U3") (pin "4") (pinfunction "GND_4") (pintype "power_in"))
      (node (ref "U4") (pin "3") (pinfunction "-VOUT_3") (pintype "output"))
      (node (ref "U5") (pin "4") (pinfunction "V-_4") (pintype "power_in"))
      (node (ref "U6") (pin "4") (pinfunction "GND_4") (pintype "power_in"))
      (node (ref "U7") (pin "4") (pinfunction "GND_4") (pintype "passive"))
      (node (ref "U8") (pin "16") (pinfunction "GND_16") (pintype "passive"))
      (node (ref "U8") (pin "9") (pinfunction "GND_2_9") (pintype "passive"))
      (node (ref "U9") (pin "2") (pinfunction "V-_2") (pintype "power_in"))
    )
    (net (code "35") (name "Net-(CR1-ADJ)") (class "Default")
      (node (ref "ADJ") (pin "TP") (pinfunction "TP_TP") (pintype "passive"))
      (node (ref "CR1") (pin "1") (pinfunction "ADJ_1") (pintype "passive"))
      (node (ref "R7") (pin "2") (pinfunction "2_2") (pintype "passive"))
      (node (ref "R8") (pin "2") (pinfunction "2_2") (pintype "passive"))
    )
    (net (code "36") (name "Net-(CR1-V-)") (class "Default")
      (node (ref "CR1") (pin "6") (pinfunction "V-_6") (pintype "power_in"))
      (node (ref "D1") (pin "2") (pinfunction "A_2") (pintype "passive"))
      (node (ref "R24") (pin "2") (pinfunction "2_2") (pintype "passive"))
      (node (ref "R7") (pin "1") (pinfunction "1_1") (pintype "passive"))
      (node (ref "V-") (pin "TP") (pinfunction "TP_TP") (pintype "passive"))
    )
    (net (code "37") (name "Net-(IC1B-+IN)") (class "Default")
      (node (ref "IC1") (pin "5") (pinfunction "+IN_5") (pintype "input"))
      (node (ref "R3") (pin "1") (pinfunction "1_1") (pintype "passive"))
      (node (ref "R4") (pin "2") (pinfunction "2_2") (pintype "passive"))
    )
    (net (code "38") (name "Net-(IC1B--IN)") (class "Default")
      (node (ref "IC1") (pin "6") (pinfunction "-IN_6") (pintype "input"))
      (node (ref "IC1") (pin "7") (pinfunction "OUT_7") (pintype "output"))
      (node (ref "REF") (pin "TP") (pinfunction "TP_TP") (pintype "passive"))
      (node (ref "U5") (pin "5") (pinfunction "REF_5") (pintype "input"))
    )
    (net (code "39") (name "Net-(IC2-CATHODE)") (class "Default")
      (node (ref "C26") (pin "1") (pinfunction "1_1") (pintype "passive"))
      (node (ref "IC2") (pin "3") (pinfunction "CATHODE_3") (pintype "bidirectional"))
      (node (ref "R17") (pin "1") (pinfunction "1_1") (pintype "passive"))
    )
    (net (code "40") (name "Net-(LED1-PadA)") (class "Default")
      (node (ref "LED1") (pin "A") (pinfunction "A_A") (pintype "passive"))
      (node (ref "R9") (pin "1") (pinfunction "1_1") (pintype "passive"))
    )
    (net (code "41") (name "Net-(U3-TRIM{slash}NR)") (class "Default")
      (node (ref "C4") (pin "1") (pinfunction "1_1") (pintype "passive"))
      (node (ref "U3") (pin "5") (pinfunction "TRIM/NR_5") (pintype "passive"))
    )
    (net (code "42") (name "Net-(U5-IN-)") (class "Default")
      (node (ref "R1") (pin "1") (pinfunction "1_1") (pintype "passive"))
      (node (ref "R18") (pin "1") (pinfunction "1_1") (pintype "passive"))
      (node (ref "R2") (pin "2") (pinfunction "2_2") (pintype "passive"))
      (node (ref "U5") (pin "2") (pinfunction "IN-_2") (pintype "input"))
      (node (ref "UIN") (pin "TP") (pinfunction "TP_TP") (pintype "passive"))
    )
    (net (code "43") (name "Net-(U5-OUT)") (class "Default")
      (node (ref "R5") (pin "2") (pinfunction "2_2") (pintype "passive"))
      (node (ref "TP11") (pin "TP") (pinfunction "TP_TP") (pintype "passive"))
      (node (ref "U5") (pin "6") (pinfunction "OUT_6") (pintype "output"))
    )
    (net (code "44") (name "Net-(U6-IN-)") (class "Default")
      (node (ref "I/O5") (pin "MP") (pinfunction "MP_MP") (pintype "passive"))
      (node (ref "R20") (pin "1") (pinfunction "1_1") (pintype "passive"))
      (node (ref "U6") (pin "2") (pinfunction "IN-_2") (pintype "input"))
      (node (ref "U6") (pin "6") (pinfunction "OUT_6") (pintype "output"))
    )
    (net (code "45") (name "Net-(U7-CLK)") (class "Default")
      (node (ref "C30") (pin "2") (pinfunction "2_2") (pintype "passive"))
      (node (ref "R13") (pin "2") (pinfunction "2_2") (pintype "passive"))
      (node (ref "SCK2") (pin "TP") (pinfunction "TP_TP") (pintype "passive"))
      (node (ref "U7") (pin "6") (pinfunction "CLK_6") (pintype "passive"))
    )
    (net (code "46") (name "Net-(U7-DI(IO0))") (class "Default")
      (node (ref "C29") (pin "1") (pinfunction "1_1") (pintype "passive"))
      (node (ref "MOSI2") (pin "TP") (pinfunction "TP_TP") (pintype "passive"))
      (node (ref "R14") (pin "2") (pinfunction "2_2") (pintype "passive"))
      (node (ref "U7") (pin "5") (pinfunction "DI(IO0)_5") (pintype "passive"))
    )
    (net (code "47") (name "Net-(U7-DO(IO1))") (class "Default")
      (node (ref "R10") (pin "1") (pinfunction "1_1") (pintype "passive"))
      (node (ref "U7") (pin "2") (pinfunction "DO(IO1)_2") (pintype "passive"))
    )
    (net (code "48") (name "Net-(U7-{slash}CS)") (class "Default")
      (node (ref "C28") (pin "2") (pinfunction "2_2") (pintype "passive"))
      (node (ref "R15") (pin "1") (pinfunction "1_1") (pintype "passive"))
      (node (ref "U7") (pin "1") (pinfunction "/CS_1") (pintype "passive"))
    )
    (net (code "49") (name "Net-(U8-CATHODE1)") (class "Default")
      (node (ref "R12") (pin "1") (pinfunction "1_1") (pintype "passive"))
      (node (ref "U8") (pin "2") (pinfunction "CATHODE1_2") (pintype "bidirectional"))
    )
    (net (code "50") (name "Net-(U8-CATHODE2)") (class "Default")
      (node (ref "R21") (pin "1") (pinfunction "1_1") (pintype "passive"))
      (node (ref "U8") (pin "4") (pinfunction "CATHODE2_4") (pintype "bidirectional"))
    )
    (net (code "51") (name "Net-(U8-CATHODE3)") (class "Default")
      (node (ref "R26") (pin "1") (pinfunction "1_1") (pintype "passive"))
      (node (ref "U8") (pin "6") (pinfunction "CATHODE3_6") (pintype "bidirectional"))
    )
    (net (code "52") (name "Net-(U8-CATHODE4)") (class "Default")
      (node (ref "R27") (pin "1") (pinfunction "1_1") (pintype "passive"))
      (node (ref "U8") (pin "8") (pinfunction "CATHODE4_8") (pintype "bidirectional"))
    )
    (net (code "53") (name "unconnected-(CR1-NC-Pad8)") (class "Default")
      (node (ref "CR1") (pin "8") (pinfunction "NC_8") (pintype "no_connect"))
    )
    (net (code "54") (name "unconnected-(CR1-NC_2-Pad2)") (class "Default")
      (node (ref "CR1") (pin "2") (pinfunction "NC_2_2") (pintype "no_connect"))
    )
    (net (code "55") (name "unconnected-(CR1-NC_3-Pad3)") (class "Default")
      (node (ref "CR1") (pin "3") (pinfunction "NC_3_3") (pintype "no_connect"))
    )
    (net (code "56") (name "unconnected-(CR1-NC_4-Pad5)") (class "Default")
      (node (ref "CR1") (pin "5") (pinfunction "NC_4_5") (pintype "no_connect"))
    )
    (net (code "57") (name "unconnected-(CR1-NC_5-Pad7)") (class "Default")
      (node (ref "CR1") (pin "7") (pinfunction "NC_5_7") (pintype "no_connect"))
    )
    (net (code "58") (name "unconnected-(IC2-N.C.-Pad2)") (class "Default")
      (node (ref "IC2") (pin "2") (pinfunction "N.C._2") (pintype "no_connect"))
    )
    (net (code "59") (name "unconnected-(U1-PA1-Pad11)") (class "Default")
      (node (ref "U1") (pin "11") (pinfunction "PA1_11") (pintype "bidirectional"))
    )
    (net (code "60") (name "unconnected-(U1-PA3-Pad13)") (class "Default")
      (node (ref "U1") (pin "13") (pinfunction "PA3_13") (pintype "bidirectional"))
    )
    (net (code "61") (name "unconnected-(U1-PA8-Pad29)") (class "Default")
      (node (ref "U1") (pin "29") (pinfunction "PA8_29") (pintype "bidirectional"))
    )
    (net (code "62") (name "unconnected-(U1-PA9-Pad30)") (class "Default")
      (node (ref "U1") (pin "30") (pinfunction "PA9_30") (pintype "bidirectional"))
    )
    (net (code "63") (name "unconnected-(U1-PA10-Pad31)") (class "Default")
      (node (ref "U1") (pin "31") (pinfunction "PA10_31") (pintype "bidirectional"))
    )
    (net (code "64") (name "unconnected-(U1-PA11-Pad32)") (class "Default")
      (node (ref "U1") (pin "32") (pinfunction "PA11_32") (pintype "bidirectional"))
    )
    (net (code "65") (name "unconnected-(U1-PA12-Pad33)") (class "Default")
      (node (ref "U1") (pin "33") (pinfunction "PA12_33") (pintype "bidirectional"))
    )
    (net (code "66") (name "unconnected-(U1-PA15-Pad38)") (class "Default")
      (node (ref "U1") (pin "38") (pinfunction "PA15_38") (pintype "bidirectional"))
    )
    (net (code "67") (name "unconnected-(U1-PB1-Pad19)") (class "Default")
      (node (ref "U1") (pin "19") (pinfunction "PB1_19") (pintype "bidirectional"))
    )
    (net (code "68") (name "unconnected-(U1-PB2-Pad20)") (class "Default")
      (node (ref "U1") (pin "20") (pinfunction "PB2_20") (pintype "bidirectional"))
    )
    (net (code "69") (name "unconnected-(U1-PB3-Pad39)") (class "Default")
      (node (ref "U1") (pin "39") (pinfunction "PB3_39") (pintype "bidirectional"))
    )
    (net (code "70") (name "unconnected-(U1-PB4-Pad40)") (class "Default")
      (node (ref "U1") (pin "40") (pinfunction "PB4_40") (pintype "bidirectional"))
    )
    (net (code "71") (name "unconnected-(U1-PB7-Pad43)") (class "Default")
      (node (ref "U1") (pin "43") (pinfunction "PB7_43") (pintype "bidirectional"))
    )
    (net (code "72") (name "unconnected-(U1-PB8-Pad45)") (class "Default")
      (node (ref "U1") (pin "45") (pinfunction "PB8_45") (pintype "bidirectional"))
    )
    (net (code "73") (name "unconnected-(U1-PB9-Pad46)") (class "Default")
      (node (ref "U1") (pin "46") (pinfunction "PB9_46") (pintype "bidirectional"))
    )
    (net (code "74") (name "unconnected-(U1-PB10-Pad21)") (class "Default")
      (node (ref "U1") (pin "21") (pinfunction "PB10_21") (pintype "bidirectional"))
    )
    (net (code "75") (name "unconnected-(U1-PB11-Pad22)") (class "Default")
      (node (ref "U1") (pin "22") (pinfunction "PB11_22") (pintype "bidirectional"))
    )
    (net (code "76") (name "unconnected-(U1-PC13-Pad2)") (class "Default")
      (node (ref "U1") (pin "2") (pinfunction "PC13_2") (pintype "bidirectional"))
    )
    (net (code "77") (name "unconnected-(U1-PC14{slash}OSC32_IN-Pad3)") (class "Default")
      (node (ref "U1") (pin "3") (pinfunction "PC14/OSC32_IN_3") (pintype "bidirectional"))
    )
    (net (code "78") (name "unconnected-(U1-PC15{slash}OSC32_OUT-Pad4)") (class "Default")
      (node (ref "U1") (pin "4") (pinfunction "PC15/OSC32_OUT_4") (pintype "bidirectional"))
    )
    (net (code "79") (name "unconnected-(U1-PH0{slash}OSC_IN-Pad5)") (class "Default")
      (node (ref "U1") (pin "5") (pinfunction "PH0/OSC_IN_5") (pintype "bidirectional"))
    )
    (net (code "80") (name "unconnected-(U1-PH1{slash}OSC_OUT-Pad6)") (class "Default")
      (node (ref "U1") (pin "6") (pinfunction "PH1/OSC_OUT_6") (pintype "bidirectional"))
    )
    (net (code "81") (name "unconnected-(U2-N{slash}C-Pad4)") (class "Default")
      (node (ref "U2") (pin "4") (pinfunction "N/C_4") (pintype "no_connect"))
    )
    (net (code "82") (name "unconnected-(U3-DNC-Pad8)") (class "Default")
      (node (ref "U3") (pin "8") (pinfunction "DNC_8") (pintype "passive"))
    )
    (net (code "83") (name "unconnected-(U3-DNC_2-Pad1)") (class "Default")
      (node (ref "U3") (pin "1") (pinfunction "DNC_2_1") (pintype "passive"))
    )
    (net (code "84") (name "unconnected-(U3-NC-Pad7)") (class "Default")
      (node (ref "U3") (pin "7") (pinfunction "NC_7") (pintype "no_connect"))
    )
    (net (code "85") (name "unconnected-(U3-TEMP-Pad3)") (class "Default")
      (node (ref "U3") (pin "3") (pinfunction "TEMP_3") (pintype "passive"))
    )
    (net (code "86") (name "unconnected-(U5-RG-Pad8)") (class "Default")
      (node (ref "U5") (pin "8") (pinfunction "RG_8") (pintype "passive"))
    )
    (net (code "87") (name "unconnected-(U5-RG_2-Pad1)") (class "Default")
      (node (ref "U5") (pin "1") (pinfunction "RG_2_1") (pintype "passive"))
    )
    (net (code "88") (name "unconnected-(U6-NC-Pad5)") (class "Default")
      (node (ref "U6") (pin "5") (pinfunction "NC_5") (pintype "passive"))
    )
    (net (code "89") (name "unconnected-(U6-NC_2-Pad1)") (class "Default")
      (node (ref "U6") (pin "1") (pinfunction "NC_2_1") (pintype "passive"))
    )
    (net (code "90") (name "unconnected-(U6-PadEPAD)") (class "Default")
      (node (ref "U6") (pin "EPAD") (pinfunction "EPAD_EPAD") (pintype "passive"))
    )
  )
)
